# RtNixie.net
KiCad netlist of a schematic drawn in EAGLE
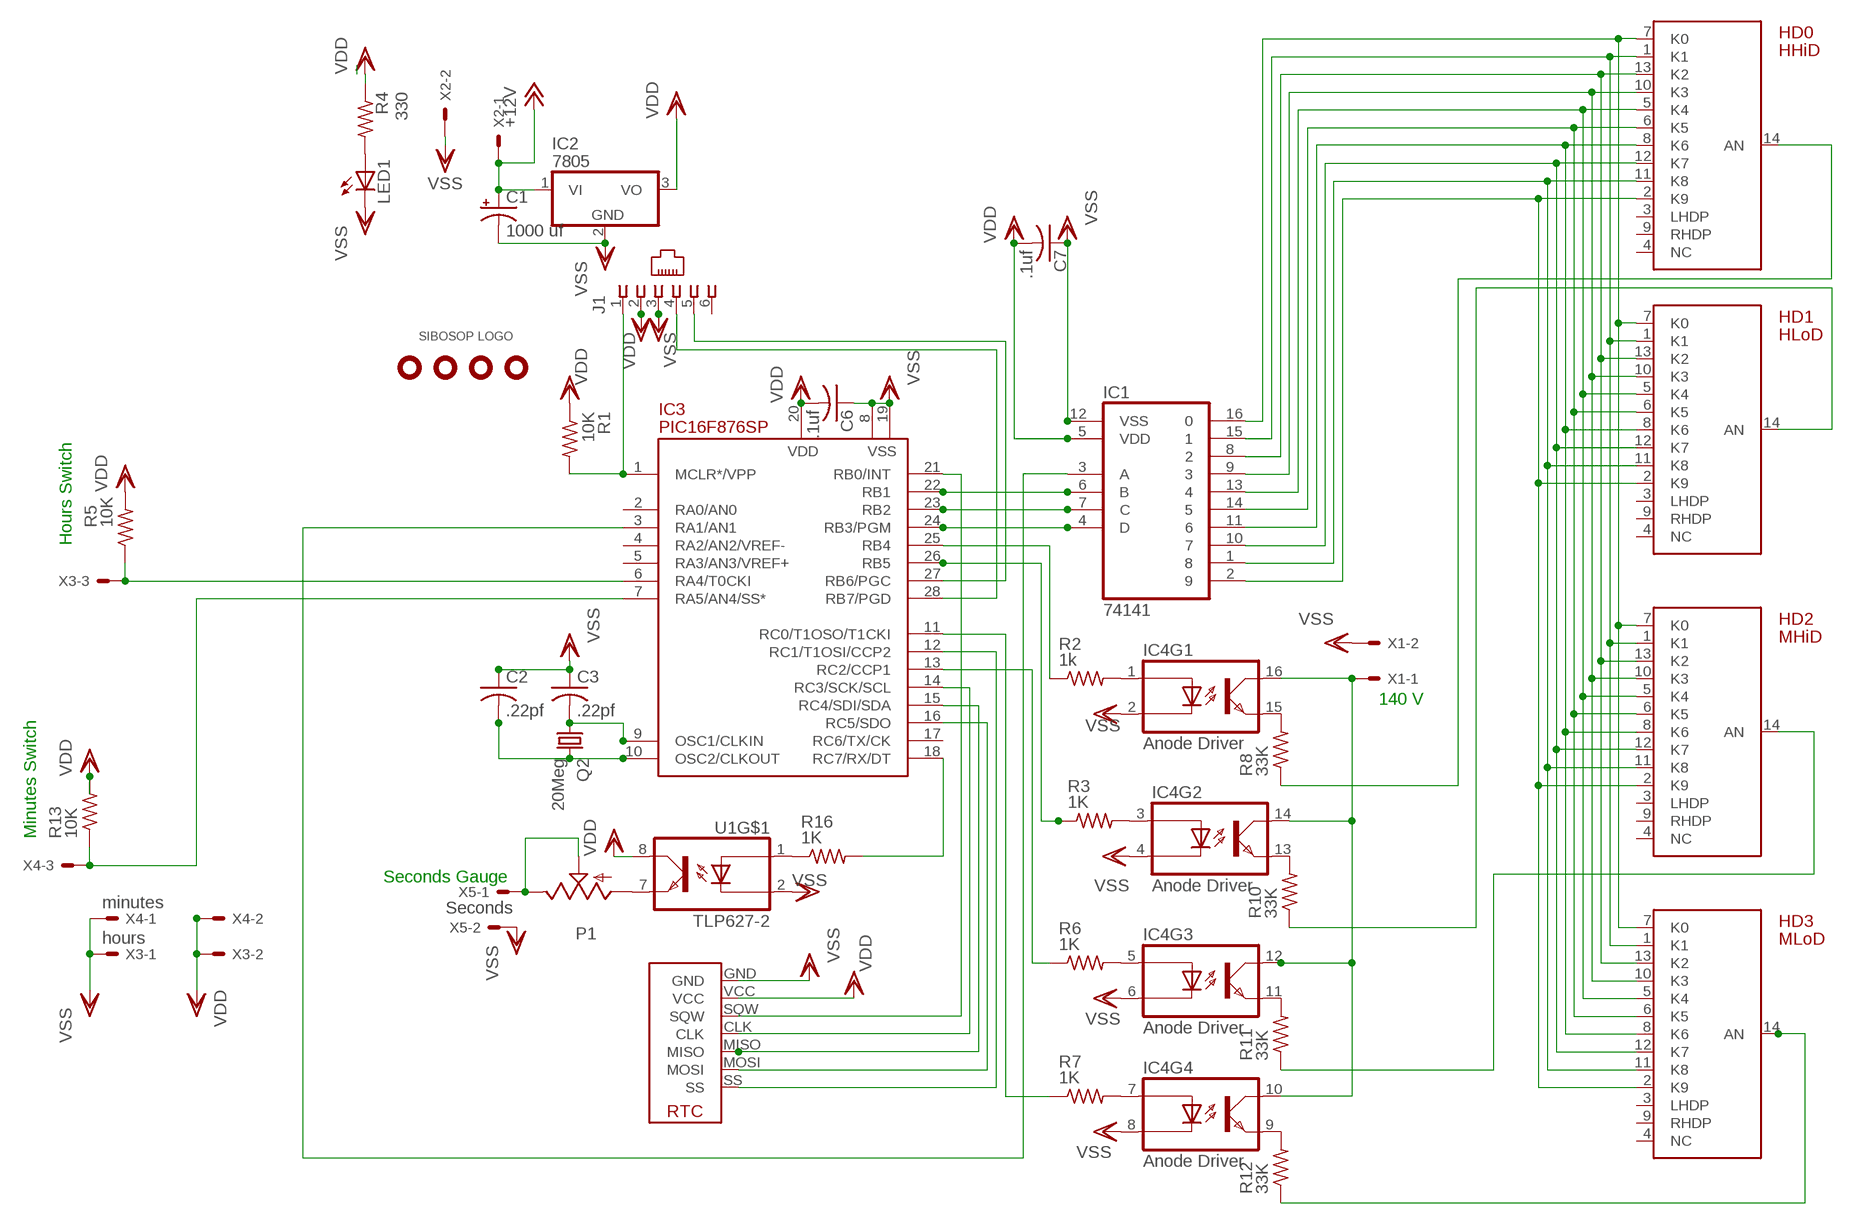
[diagram p0: schematic, sheet 1]

(export (version "E")
  (design (tool "Eeschema 10.0.6"))
  (components
    (comp (ref "C1")
      (value "1000 uf")
      (footprint "eagle-import:E3,5-10")
      (libsource (lib "eagle-import") (part "CPOL-USE3.5-10"))
    )
    (comp (ref "C2")
      (value ".22pf")
      (footprint "eagle-import:C025-024X044")
      (libsource (lib "eagle-import") (part "C-US025-024X044"))
    )
    (comp (ref "C3")
      (value ".22pf")
      (footprint "eagle-import:C025-024X044")
      (libsource (lib "eagle-import") (part "C-US025-024X044"))
    )
    (comp (ref "C6")
      (value ".1uf")
      (footprint "eagle-import:C025-024X044")
      (libsource (lib "eagle-import") (part "C-US025-024X044"))
    )
    (comp (ref "C7")
      (value ".1uf")
      (footprint "eagle-import:C025-024X044")
      (libsource (lib "eagle-import") (part "C-US025-024X044"))
    )
    (comp (ref "HD0")
      (value "HHiD")
      (footprint "eagle-import:DIL14")
      (libsource (lib "eagle-import") (part "NIXIE-5440-HEADER"))
    )
    (comp (ref "HD1")
      (value "HLoD")
      (footprint "eagle-import:DIL14")
      (libsource (lib "eagle-import") (part "NIXIE-5440-HEADER"))
    )
    (comp (ref "HD2")
      (value "MHiD")
      (footprint "eagle-import:DIL14")
      (libsource (lib "eagle-import") (part "NIXIE-5440-HEADER"))
    )
    (comp (ref "HD3")
      (value "MLoD")
      (footprint "eagle-import:DIL14")
      (libsource (lib "eagle-import") (part "NIXIE-5440-HEADER"))
    )
    (comp (ref "IC1")
      (value "74141")
      (footprint "eagle-import:DIP16")
      (libsource (lib "eagle-import") (part "74141"))
    )
    (comp (ref "IC2")
      (value "7805")
      (footprint "eagle-import:TO220V")
      (libsource (lib "eagle-import") (part "7805"))
    )
    (comp (ref "IC3")
      (value "PIC16F876SP")
      (footprint "eagle-import:DIL28-3")
      (libsource (lib "eagle-import") (part "PIC16F876SP"))
    )
    (comp (ref "IC4")
      (value "Anode Driver")
      (footprint "eagle-import:DIP16")
      (libsource (lib "eagle-import") (part "TLP627"))
    )
    (comp (ref "IC5")
      (value "SPARKRTC")
      (footprint "eagle-import:SPARKRTC")
      (libsource (lib "eagle-import") (part "SPARKRTC"))
    )
    (comp (ref "J1")
      (value "520250-3")
      (footprint "eagle-import:520250-3")
      (libsource (lib "eagle-import") (part "520250-3"))
    )
    (comp (ref "LED1")
      (value "LEDSQR2X5")
      (footprint "eagle-import:LED2X5")
      (libsource (lib "eagle-import") (part "LEDSQR2X5"))
    )
    (comp (ref "P1")
      (value "TRIMPOT")
      (footprint "eagle-import:RJ6S")
      (libsource (lib "eagle-import") (part "TRIMPOT"))
    )
    (comp (ref "Q2")
      (value "20Meg")
      (footprint "eagle-import:HC49_S")
      (libsource (lib "eagle-import") (part "CRYSTALHC49S"))
    )
    (comp (ref "R1")
      (value "10K")
      (footprint "eagle-import:0204V")
      (libsource (lib "eagle-import") (part "R-US_0204/2V"))
    )
    (comp (ref "R2")
      (value "1k")
      (footprint "eagle-import:0204V")
      (libsource (lib "eagle-import") (part "R-US_0204/2V"))
    )
    (comp (ref "R3")
      (value "1K")
      (footprint "eagle-import:0204V")
      (libsource (lib "eagle-import") (part "R-US_0204/2V"))
    )
    (comp (ref "R4")
      (value "330")
      (footprint "eagle-import:0204V")
      (libsource (lib "eagle-import") (part "R-US_0204/2V"))
    )
    (comp (ref "R5")
      (value "10K")
      (footprint "eagle-import:0204V")
      (libsource (lib "eagle-import") (part "R-US_0204/2V"))
    )
    (comp (ref "R6")
      (value "1K")
      (footprint "eagle-import:0204V")
      (libsource (lib "eagle-import") (part "R-US_0204/2V"))
    )
    (comp (ref "R7")
      (value "1K")
      (footprint "eagle-import:0204V")
      (libsource (lib "eagle-import") (part "R-US_0204/2V"))
    )
    (comp (ref "R8")
      (value "33K")
      (footprint "eagle-import:0204V")
      (libsource (lib "eagle-import") (part "R-US_0204/2V"))
    )
    (comp (ref "R10")
      (value "33K")
      (footprint "eagle-import:0204V")
      (libsource (lib "eagle-import") (part "R-US_0204/2V"))
    )
    (comp (ref "R11")
      (value "33K")
      (footprint "eagle-import:0204V")
      (libsource (lib "eagle-import") (part "R-US_0204/2V"))
    )
    (comp (ref "R12")
      (value "33K")
      (footprint "eagle-import:0204V")
      (libsource (lib "eagle-import") (part "R-US_0204/2V"))
    )
    (comp (ref "R13")
      (value "10K")
      (footprint "eagle-import:0204V")
      (libsource (lib "eagle-import") (part "R-US_0204/2V"))
    )
    (comp (ref "R16")
      (value "1K")
      (footprint "eagle-import:0204V")
      (libsource (lib "eagle-import") (part "R-US_0204/2V"))
    )
    (comp (ref "U$1")
      (value "HOLE-125")
      (footprint "eagle-import:HOLE-125")
      (libsource (lib "eagle-import") (part "HOLE-125"))
    )
    (comp (ref "U$2")
      (value "HOLE-125")
      (footprint "eagle-import:HOLE-125")
      (libsource (lib "eagle-import") (part "HOLE-125"))
    )
    (comp (ref "U$3")
      (value "LOGO")
      (footprint "eagle-import:LOGO")
      (libsource (lib "eagle-import") (part "LOGO"))
    )
    (comp (ref "U$5")
      (value "HOLE-125")
      (footprint "eagle-import:HOLE-125")
      (libsource (lib "eagle-import") (part "HOLE-125"))
    )
    (comp (ref "U$7")
      (value "HOLE-125")
      (footprint "eagle-import:HOLE-125")
      (libsource (lib "eagle-import") (part "HOLE-125"))
    )
    (comp (ref "U1")
      (value "TLP627-2")
      (footprint "eagle-import:DIL8")
      (libsource (lib "eagle-import") (part "TLP627-2"))
    )
    (comp (ref "X1")
      (value "22-23-2021")
      (footprint "eagle-import:22-23-2021")
      (libsource (lib "eagle-import") (part "22-23-2021"))
    )
    (comp (ref "X2")
      (value "22-23-2021")
      (footprint "eagle-import:22-23-2021")
      (libsource (lib "eagle-import") (part "22-23-2021"))
    )
    (comp (ref "X3")
      (value "hours")
      (footprint "eagle-import:22-23-2031")
      (libsource (lib "eagle-import") (part "22-23-2031"))
    )
    (comp (ref "X4")
      (value "minutes")
      (footprint "eagle-import:22-23-2031")
      (libsource (lib "eagle-import") (part "22-23-2031"))
    )
    (comp (ref "X5")
      (value "Seconds")
      (footprint "eagle-import:22-23-2021")
      (libsource (lib "eagle-import") (part "22-23-2021"))
    )
  )
  (nets
    (net (code "1") (name "+12V") (class "Default")
      (node (ref "C1") (pin "+") (pinfunction "+_+") (pintype "passive"))
      (node (ref "IC2") (pin "1") (pinfunction "VI_1") (pintype "input"))
      (node (ref "X2") (pin "1") (pinfunction "S_1") (pintype "passive"))
    )
    (net (code "2") (name "Net-(HD0-AN)") (class "Default")
      (node (ref "HD0") (pin "14") (pinfunction "AN_14") (pintype "passive"))
      (node (ref "R8") (pin "1") (pinfunction "1_1") (pintype "passive"))
    )
    (net (code "3") (name "Net-(HD0-K0)") (class "Default")
      (node (ref "HD0") (pin "7") (pinfunction "K0_7") (pintype "passive"))
      (node (ref "HD1") (pin "7") (pinfunction "K0_7") (pintype "passive"))
      (node (ref "HD2") (pin "7") (pinfunction "K0_7") (pintype "passive"))
      (node (ref "HD3") (pin "7") (pinfunction "K0_7") (pintype "passive"))
      (node (ref "IC1") (pin "16") (pinfunction "0_16") (pintype "open_collector"))
    )
    (net (code "4") (name "Net-(HD0-K1)") (class "Default")
      (node (ref "HD0") (pin "1") (pinfunction "K1_1") (pintype "passive"))
      (node (ref "HD1") (pin "1") (pinfunction "K1_1") (pintype "passive"))
      (node (ref "HD2") (pin "1") (pinfunction "K1_1") (pintype "passive"))
      (node (ref "HD3") (pin "1") (pinfunction "K1_1") (pintype "passive"))
      (node (ref "IC1") (pin "15") (pinfunction "1_15") (pintype "open_collector"))
    )
    (net (code "5") (name "Net-(HD0-K2)") (class "Default")
      (node (ref "HD0") (pin "13") (pinfunction "K2_13") (pintype "passive"))
      (node (ref "HD1") (pin "13") (pinfunction "K2_13") (pintype "passive"))
      (node (ref "HD2") (pin "13") (pinfunction "K2_13") (pintype "passive"))
      (node (ref "HD3") (pin "13") (pinfunction "K2_13") (pintype "passive"))
      (node (ref "IC1") (pin "8") (pinfunction "2_8") (pintype "open_collector"))
    )
    (net (code "6") (name "Net-(HD0-K3)") (class "Default")
      (node (ref "HD0") (pin "10") (pinfunction "K3_10") (pintype "passive"))
      (node (ref "HD1") (pin "10") (pinfunction "K3_10") (pintype "passive"))
      (node (ref "HD2") (pin "10") (pinfunction "K3_10") (pintype "passive"))
      (node (ref "HD3") (pin "10") (pinfunction "K3_10") (pintype "passive"))
      (node (ref "IC1") (pin "9") (pinfunction "3_9") (pintype "open_collector"))
    )
    (net (code "7") (name "Net-(HD0-K4)") (class "Default")
      (node (ref "HD0") (pin "5") (pinfunction "K4_5") (pintype "passive"))
      (node (ref "HD1") (pin "5") (pinfunction "K4_5") (pintype "passive"))
      (node (ref "HD2") (pin "5") (pinfunction "K4_5") (pintype "passive"))
      (node (ref "HD3") (pin "5") (pinfunction "K4_5") (pintype "passive"))
      (node (ref "IC1") (pin "13") (pinfunction "4_13") (pintype "open_collector"))
    )
    (net (code "8") (name "Net-(HD0-K5)") (class "Default")
      (node (ref "HD0") (pin "6") (pinfunction "K5_6") (pintype "passive"))
      (node (ref "HD1") (pin "6") (pinfunction "K5_6") (pintype "passive"))
      (node (ref "HD2") (pin "6") (pinfunction "K5_6") (pintype "passive"))
      (node (ref "HD3") (pin "6") (pinfunction "K5_6") (pintype "passive"))
      (node (ref "IC1") (pin "14") (pinfunction "5_14") (pintype "open_collector"))
    )
    (net (code "9") (name "Net-(HD0-K6)") (class "Default")
      (node (ref "HD0") (pin "8") (pinfunction "K6_8") (pintype "passive"))
      (node (ref "HD1") (pin "8") (pinfunction "K6_8") (pintype "passive"))
      (node (ref "HD2") (pin "8") (pinfunction "K6_8") (pintype "passive"))
      (node (ref "HD3") (pin "8") (pinfunction "K6_8") (pintype "passive"))
      (node (ref "IC1") (pin "11") (pinfunction "6_11") (pintype "open_collector"))
    )
    (net (code "10") (name "Net-(HD0-K7)") (class "Default")
      (node (ref "HD0") (pin "12") (pinfunction "K7_12") (pintype "passive"))
      (node (ref "HD1") (pin "12") (pinfunction "K7_12") (pintype "passive"))
      (node (ref "HD2") (pin "12") (pinfunction "K7_12") (pintype "passive"))
      (node (ref "HD3") (pin "12") (pinfunction "K7_12") (pintype "passive"))
      (node (ref "IC1") (pin "10") (pinfunction "7_10") (pintype "open_collector"))
    )
    (net (code "11") (name "Net-(HD0-K8)") (class "Default")
      (node (ref "HD0") (pin "11") (pinfunction "K8_11") (pintype "passive"))
      (node (ref "HD1") (pin "11") (pinfunction "K8_11") (pintype "passive"))
      (node (ref "HD2") (pin "11") (pinfunction "K8_11") (pintype "passive"))
      (node (ref "HD3") (pin "11") (pinfunction "K8_11") (pintype "passive"))
      (node (ref "IC1") (pin "1") (pinfunction "8_1") (pintype "open_collector"))
    )
    (net (code "12") (name "Net-(HD0-K9)") (class "Default")
      (node (ref "HD0") (pin "2") (pinfunction "K9_2") (pintype "passive"))
      (node (ref "HD1") (pin "2") (pinfunction "K9_2") (pintype "passive"))
      (node (ref "HD2") (pin "2") (pinfunction "K9_2") (pintype "passive"))
      (node (ref "HD3") (pin "2") (pinfunction "K9_2") (pintype "passive"))
      (node (ref "IC1") (pin "2") (pinfunction "9_2") (pintype "open_collector"))
    )
    (net (code "13") (name "Net-(HD1-AN)") (class "Default")
      (node (ref "HD1") (pin "14") (pinfunction "AN_14") (pintype "passive"))
      (node (ref "R10") (pin "1") (pinfunction "1_1") (pintype "passive"))
    )
    (net (code "14") (name "Net-(HD2-AN)") (class "Default")
      (node (ref "HD2") (pin "14") (pinfunction "AN_14") (pintype "passive"))
      (node (ref "R11") (pin "1") (pinfunction "1_1") (pintype "passive"))
    )
    (net (code "15") (name "Net-(HD3-AN)") (class "Default")
      (node (ref "HD3") (pin "14") (pinfunction "AN_14") (pintype "passive"))
      (node (ref "R12") (pin "1") (pinfunction "1_1") (pintype "passive"))
    )
    (net (code "16") (name "Net-(IC1-A)") (class "Default")
      (node (ref "IC1") (pin "3") (pinfunction "A_3") (pintype "input"))
      (node (ref "IC3") (pin "3") (pinfunction "RA1/AN1_3") (pintype "bidirectional"))
    )
    (net (code "17") (name "Net-(IC1-B)") (class "Default")
      (node (ref "IC1") (pin "6") (pinfunction "B_6") (pintype "input"))
      (node (ref "IC3") (pin "22") (pinfunction "RB1_22") (pintype "bidirectional"))
    )
    (net (code "18") (name "Net-(IC1-C)") (class "Default")
      (node (ref "IC1") (pin "7") (pinfunction "C_7") (pintype "input"))
      (node (ref "IC3") (pin "23") (pinfunction "RB2_23") (pintype "bidirectional"))
    )
    (net (code "19") (name "Net-(IC1-D)") (class "Default")
      (node (ref "IC1") (pin "4") (pinfunction "D_4") (pintype "input"))
      (node (ref "IC3") (pin "24") (pinfunction "RB3/PGM_24") (pintype "bidirectional"))
    )
    (net (code "20") (name "Net-(IC3-MCLR*{slash}VPP)") (class "Default")
      (node (ref "IC3") (pin "1") (pinfunction "MCLR*/VPP_1") (pintype "bidirectional"))
      (node (ref "J1") (pin "1") (pinfunction "1_1") (pintype "passive"))
      (node (ref "R1") (pin "2") (pinfunction "2_2") (pintype "passive"))
    )
    (net (code "21") (name "Net-(IC3-OSC1{slash}CLKIN)") (class "Default")
      (node (ref "C3") (pin "2") (pinfunction "2_2") (pintype "passive"))
      (node (ref "IC3") (pin "9") (pinfunction "OSC1/CLKIN_9") (pintype "bidirectional"))
      (node (ref "Q2") (pin "1") (pinfunction "1_1") (pintype "passive"))
    )
    (net (code "22") (name "Net-(IC3-OSC2{slash}CLKOUT)") (class "Default")
      (node (ref "C2") (pin "2") (pinfunction "2_2") (pintype "passive"))
      (node (ref "IC3") (pin "10") (pinfunction "OSC2/CLKOUT_10") (pintype "bidirectional"))
      (node (ref "Q2") (pin "2") (pinfunction "2_2") (pintype "passive"))
    )
    (net (code "23") (name "Net-(IC3-RA4{slash}T0CKI)") (class "Default")
      (node (ref "IC3") (pin "6") (pinfunction "RA4/T0CKI_6") (pintype "bidirectional"))
      (node (ref "R5") (pin "1") (pinfunction "1_1") (pintype "passive"))
      (node (ref "X3") (pin "3") (pinfunction "S_3") (pintype "passive"))
    )
    (net (code "24") (name "Net-(IC3-RA5{slash}AN4{slash}SS*)") (class "Default")
      (node (ref "IC3") (pin "7") (pinfunction "RA5/AN4/SS*_7") (pintype "bidirectional"))
      (node (ref "R13") (pin "1") (pinfunction "1_1") (pintype "passive"))
      (node (ref "X4") (pin "3") (pinfunction "S_3") (pintype "passive"))
    )
    (net (code "25") (name "Net-(IC3-RB0{slash}INT)") (class "Default")
      (node (ref "IC3") (pin "21") (pinfunction "RB0/INT_21") (pintype "bidirectional"))
      (node (ref "IC5") (pin "SQW") (pinfunction "SQW_SQW") (pintype "bidirectional"))
    )
    (net (code "26") (name "Net-(IC3-RB4)") (class "Default")
      (node (ref "IC3") (pin "25") (pinfunction "RB4_25") (pintype "bidirectional"))
      (node (ref "R2") (pin "1") (pinfunction "1_1") (pintype "passive"))
    )
    (net (code "27") (name "Net-(IC3-RB5)") (class "Default")
      (node (ref "IC3") (pin "26") (pinfunction "RB5_26") (pintype "bidirectional"))
      (node (ref "R3") (pin "1") (pinfunction "1_1") (pintype "passive"))
    )
    (net (code "28") (name "Net-(IC3-RB6{slash}PGC)") (class "Default")
      (node (ref "IC3") (pin "27") (pinfunction "RB6/PGC_27") (pintype "bidirectional"))
      (node (ref "J1") (pin "5") (pinfunction "5_5") (pintype "passive"))
    )
    (net (code "29") (name "Net-(IC3-RB7{slash}PGD)") (class "Default")
      (node (ref "IC3") (pin "28") (pinfunction "RB7/PGD_28") (pintype "bidirectional"))
      (node (ref "J1") (pin "4") (pinfunction "4_4") (pintype "passive"))
    )
    (net (code "30") (name "Net-(IC3-RC0{slash}T1OSO{slash}T1CKI)") (class "Default")
      (node (ref "IC3") (pin "11") (pinfunction "RC0/T1OSO/T1CKI_11") (pintype "bidirectional"))
      (node (ref "R7") (pin "1") (pinfunction "1_1") (pintype "passive"))
    )
    (net (code "31") (name "Net-(IC3-RC1{slash}T1OSI{slash}CCP2)") (class "Default")
      (node (ref "IC3") (pin "12") (pinfunction "RC1/T1OSI/CCP2_12") (pintype "bidirectional"))
      (node (ref "IC5") (pin "SS") (pinfunction "SS_SS") (pintype "bidirectional"))
    )
    (net (code "32") (name "Net-(IC3-RC2{slash}CCP1)") (class "Default")
      (node (ref "IC3") (pin "13") (pinfunction "RC2/CCP1_13") (pintype "bidirectional"))
      (node (ref "R6") (pin "1") (pinfunction "1_1") (pintype "passive"))
    )
    (net (code "33") (name "Net-(IC3-RC3{slash}SCK{slash}SCL)") (class "Default")
      (node (ref "IC3") (pin "14") (pinfunction "RC3/SCK/SCL_14") (pintype "bidirectional"))
      (node (ref "IC5") (pin "CLK") (pinfunction "CLK_CLK") (pintype "bidirectional"))
    )
    (net (code "34") (name "Net-(IC3-RC4{slash}SDI{slash}SDA)") (class "Default")
      (node (ref "IC3") (pin "15") (pinfunction "RC4/SDI/SDA_15") (pintype "bidirectional"))
      (node (ref "IC5") (pin "MISO") (pinfunction "MISO_MISO") (pintype "bidirectional"))
    )
    (net (code "35") (name "Net-(IC3-RC5{slash}SDO)") (class "Default")
      (node (ref "IC3") (pin "16") (pinfunction "RC5/SDO_16") (pintype "bidirectional"))
      (node (ref "IC5") (pin "MOSI") (pinfunction "MOSI_MOSI") (pintype "bidirectional"))
    )
    (net (code "36") (name "Net-(IC3-RC7{slash}RX{slash}DT)") (class "Default")
      (node (ref "IC3") (pin "18") (pinfunction "RC7/RX/DT_18") (pintype "bidirectional"))
      (node (ref "R16") (pin "2") (pinfunction "2_2") (pintype "passive"))
    )
    (net (code "37") (name "Net-(IC4A-AN)") (class "Default")
      (node (ref "IC4") (pin "1") (pinfunction "AN_1") (pintype "passive"))
      (node (ref "R2") (pin "2") (pinfunction "2_2") (pintype "passive"))
    )
    (net (code "38") (name "Net-(IC4A-CO)") (class "Default")
      (node (ref "IC4") (pin "10") (pinfunction "CO_10") (pintype "passive"))
      (node (ref "IC4") (pin "12") (pinfunction "CO_12") (pintype "passive"))
      (node (ref "IC4") (pin "14") (pinfunction "CO_14") (pintype "passive"))
      (node (ref "IC4") (pin "16") (pinfunction "CO_16") (pintype "passive"))
      (node (ref "X1") (pin "1") (pinfunction "S_1") (pintype "passive"))
    )
    (net (code "39") (name "Net-(IC4A-EM)") (class "Default")
      (node (ref "IC4") (pin "15") (pinfunction "EM_15") (pintype "passive"))
      (node (ref "R8") (pin "2") (pinfunction "2_2") (pintype "passive"))
    )
    (net (code "40") (name "Net-(IC4B-AN)") (class "Default")
      (node (ref "IC4") (pin "3") (pinfunction "AN_3") (pintype "passive"))
      (node (ref "R3") (pin "2") (pinfunction "2_2") (pintype "passive"))
    )
    (net (code "41") (name "Net-(IC4B-EM)") (class "Default")
      (node (ref "IC4") (pin "13") (pinfunction "EM_13") (pintype "passive"))
      (node (ref "R10") (pin "2") (pinfunction "2_2") (pintype "passive"))
    )
    (net (code "42") (name "Net-(IC4C-AN)") (class "Default")
      (node (ref "IC4") (pin "5") (pinfunction "AN_5") (pintype "passive"))
      (node (ref "R6") (pin "2") (pinfunction "2_2") (pintype "passive"))
    )
    (net (code "43") (name "Net-(IC4C-EM)") (class "Default")
      (node (ref "IC4") (pin "11") (pinfunction "EM_11") (pintype "passive"))
      (node (ref "R11") (pin "2") (pinfunction "2_2") (pintype "passive"))
    )
    (net (code "44") (name "Net-(IC4D-AN)") (class "Default")
      (node (ref "IC4") (pin "7") (pinfunction "AN_7") (pintype "passive"))
      (node (ref "R7") (pin "2") (pinfunction "2_2") (pintype "passive"))
    )
    (net (code "45") (name "Net-(IC4D-EM)") (class "Default")
      (node (ref "IC4") (pin "9") (pinfunction "EM_9") (pintype "passive"))
      (node (ref "R12") (pin "2") (pinfunction "2_2") (pintype "passive"))
    )
    (net (code "46") (name "Net-(LED1-PadA)") (class "Default")
      (node (ref "LED1") (pin "A") (pinfunction "A_A") (pintype "passive"))
      (node (ref "R4") (pin "2") (pinfunction "2_2") (pintype "passive"))
    )
    (net (code "47") (name "Net-(U1A-AN)") (class "Default")
      (node (ref "R16") (pin "1") (pinfunction "1_1") (pintype "passive"))
      (node (ref "U1") (pin "1") (pinfunction "AN_1") (pintype "passive"))
    )
    (net (code "48") (name "Net-(U1A-EM)") (class "Default")
      (node (ref "P1") (pin "A") (pinfunction "A_A") (pintype "passive"))
      (node (ref "U1") (pin "7") (pinfunction "EM_7") (pintype "passive"))
    )
    (net (code "49") (name "Net-(X5A-S)") (class "Default")
      (node (ref "P1") (pin "E") (pinfunction "E_E") (pintype "passive"))
      (node (ref "P1") (pin "S") (pinfunction "S_S") (pintype "passive"))
      (node (ref "X5") (pin "1") (pinfunction "S_1") (pintype "passive"))
    )
    (net (code "50") (name "VDD") (class "Default")
      (node (ref "C6") (pin "2") (pinfunction "2_2") (pintype "passive"))
      (node (ref "C7") (pin "2") (pinfunction "2_2") (pintype "passive"))
      (node (ref "IC1") (pin "5") (pinfunction "VDD_5") (pintype "power_in"))
      (node (ref "IC2") (pin "3") (pinfunction "VO_3") (pintype "passive"))
      (node (ref "IC3") (pin "20") (pinfunction "VDD_20") (pintype "power_in"))
      (node (ref "IC5") (pin "VCC") (pinfunction "VCC_VCC") (pintype "power_in"))
      (node (ref "J1") (pin "2") (pinfunction "2_2") (pintype "passive"))
      (node (ref "R1") (pin "1") (pinfunction "1_1") (pintype "passive"))
      (node (ref "R13") (pin "2") (pinfunction "2_2") (pintype "passive"))
      (node (ref "R4") (pin "1") (pinfunction "1_1") (pintype "passive"))
      (node (ref "R5") (pin "2") (pinfunction "2_2") (pintype "passive"))
      (node (ref "U1") (pin "8") (pinfunction "CO_8") (pintype "passive"))
      (node (ref "X3") (pin "2") (pinfunction "S_2") (pintype "passive"))
      (node (ref "X4") (pin "2") (pinfunction "S_2") (pintype "passive"))
    )
    (net (code "51") (name "VSS") (class "Default")
      (node (ref "C1") (pin "-") (pinfunction "-_-") (pintype "passive"))
      (node (ref "C2") (pin "1") (pinfunction "1_1") (pintype "passive"))
      (node (ref "C3") (pin "1") (pinfunction "1_1") (pintype "passive"))
      (node (ref "C6") (pin "1") (pinfunction "1_1") (pintype "passive"))
      (node (ref "C7") (pin "1") (pinfunction "1_1") (pintype "passive"))
      (node (ref "IC1") (pin "12") (pinfunction "VSS_12") (pintype "power_in"))
      (node (ref "IC2") (pin "2") (pinfunction "GND_2") (pintype "passive"))
      (node (ref "IC3") (pin "19") (pinfunction "VSS_19") (pintype "power_in"))
      (node (ref "IC3") (pin "8") (pinfunction "VSS_8") (pintype "power_in"))
      (node (ref "IC4") (pin "2") (pinfunction "CA_2") (pintype "passive"))
      (node (ref "IC4") (pin "4") (pinfunction "CA_4") (pintype "passive"))
      (node (ref "IC4") (pin "6") (pinfunction "CA_6") (pintype "passive"))
      (node (ref "IC4") (pin "8") (pinfunction "CA_8") (pintype "passive"))
      (node (ref "IC5") (pin "GND") (pinfunction "GND_GND") (pintype "power_in"))
      (node (ref "J1") (pin "3") (pinfunction "3_3") (pintype "passive"))
      (node (ref "LED1") (pin "K") (pinfunction "C_K") (pintype "passive"))
      (node (ref "U1") (pin "2") (pinfunction "CA_2") (pintype "passive"))
      (node (ref "X1") (pin "2") (pinfunction "S_2") (pintype "passive"))
      (node (ref "X2") (pin "2") (pinfunction "S_2") (pintype "passive"))
      (node (ref "X3") (pin "1") (pinfunction "S_1") (pintype "passive"))
      (node (ref "X4") (pin "1") (pinfunction "S_1") (pintype "passive"))
      (node (ref "X5") (pin "2") (pinfunction "S_2") (pintype "passive"))
    )
    (net (code "52") (name "unconnected-(HD0-LHDP-Pad3)") (class "Default")
      (node (ref "HD0") (pin "3") (pinfunction "LHDP_3") (pintype "passive"))
    )
    (net (code "53") (name "unconnected-(HD0-NC-Pad4)") (class "Default")
      (node (ref "HD0") (pin "4") (pinfunction "NC_4") (pintype "passive"))
    )
    (net (code "54") (name "unconnected-(HD0-RHDP-Pad9)") (class "Default")
      (node (ref "HD0") (pin "9") (pinfunction "RHDP_9") (pintype "passive"))
    )
    (net (code "55") (name "unconnected-(HD1-LHDP-Pad3)") (class "Default")
      (node (ref "HD1") (pin "3") (pinfunction "LHDP_3") (pintype "passive"))
    )
    (net (code "56") (name "unconnected-(HD1-NC-Pad4)") (class "Default")
      (node (ref "HD1") (pin "4") (pinfunction "NC_4") (pintype "passive"))
    )
    (net (code "57") (name "unconnected-(HD1-RHDP-Pad9)") (class "Default")
      (node (ref "HD1") (pin "9") (pinfunction "RHDP_9") (pintype "passive"))
    )
    (net (code "58") (name "unconnected-(HD2-LHDP-Pad3)") (class "Default")
      (node (ref "HD2") (pin "3") (pinfunction "LHDP_3") (pintype "passive"))
    )
    (net (code "59") (name "unconnected-(HD2-NC-Pad4)") (class "Default")
      (node (ref "HD2") (pin "4") (pinfunction "NC_4") (pintype "passive"))
    )
    (net (code "60") (name "unconnected-(HD2-RHDP-Pad9)") (class "Default")
      (node (ref "HD2") (pin "9") (pinfunction "RHDP_9") (pintype "passive"))
    )
    (net (code "61") (name "unconnected-(HD3-LHDP-Pad3)") (class "Default")
      (node (ref "HD3") (pin "3") (pinfunction "LHDP_3") (pintype "passive"))
    )
    (net (code "62") (name "unconnected-(HD3-NC-Pad4)") (class "Default")
      (node (ref "HD3") (pin "4") (pinfunction "NC_4") (pintype "passive"))
    )
    (net (code "63") (name "unconnected-(HD3-RHDP-Pad9)") (class "Default")
      (node (ref "HD3") (pin "9") (pinfunction "RHDP_9") (pintype "passive"))
    )
    (net (code "64") (name "unconnected-(IC3-RA0{slash}AN0-Pad2)") (class "Default")
      (node (ref "IC3") (pin "2") (pinfunction "RA0/AN0_2") (pintype "bidirectional"))
    )
    (net (code "65") (name "unconnected-(IC3-RA2{slash}AN2{slash}VREF--Pad4)") (class "Default")
      (node (ref "IC3") (pin "4") (pinfunction "RA2/AN2/VREF-_4") (pintype "bidirectional"))
    )
    (net (code "66") (name "unconnected-(IC3-RA3{slash}AN3{slash}VREF+-Pad5)") (class "Default")
      (node (ref "IC3") (pin "5") (pinfunction "RA3/AN3/VREF+_5") (pintype "bidirectional"))
    )
    (net (code "67") (name "unconnected-(IC3-RC6{slash}TX{slash}CK-Pad17)") (class "Default")
      (node (ref "IC3") (pin "17") (pinfunction "RC6/TX/CK_17") (pintype "bidirectional"))
    )
    (net (code "68") (name "unconnected-(J1-Pad6)") (class "Default")
      (node (ref "J1") (pin "6") (pinfunction "6_6") (pintype "passive"))
    )
  )
)
